# ProPrj_usb__2025-12-14-12-24-50.net
KiCad netlist of a schematic drawn in EasyEDA Pro
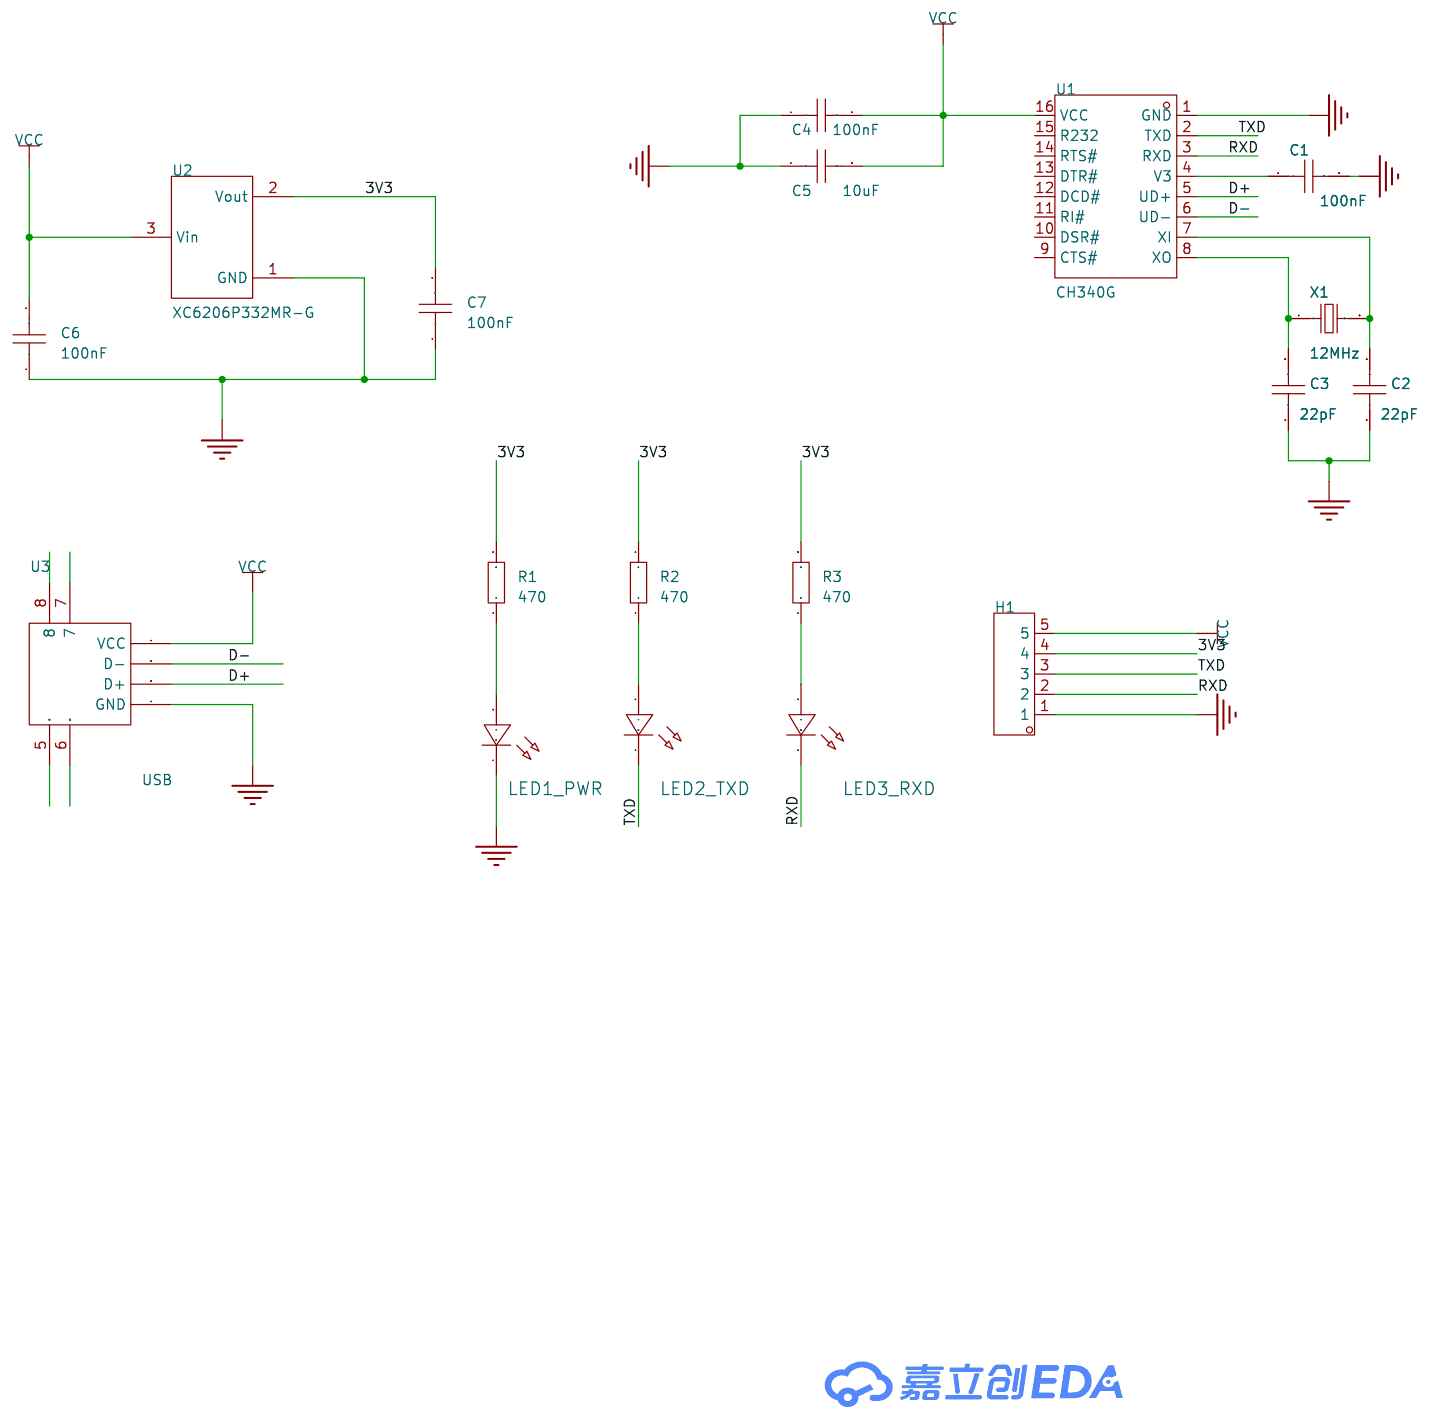
[diagram p0: schematic sheet]

(export (version "E")
  (design (tool "Eeschema 10.0.6"))
  (components
    (comp (ref "C1")
      (value "100nF")
      (footprint "easyedapro:C0603")
      (libsource (lib "easyedapro") (part "Capacitance"))
    )
    (comp (ref "C2")
      (value "22pF")
      (footprint "easyedapro:C0603")
      (libsource (lib "easyedapro") (part "Capacitance"))
    )
    (comp (ref "C3")
      (value "22pF")
      (footprint "easyedapro:C0603")
      (libsource (lib "easyedapro") (part "Capacitance"))
    )
    (comp (ref "C4")
      (value "100nF")
      (footprint "easyedapro:C0603")
      (libsource (lib "easyedapro") (part "Capacitance"))
    )
    (comp (ref "C5")
      (value "10uF")
      (footprint "easyedapro:C0603")
      (libsource (lib "easyedapro") (part "Capacitance"))
    )
    (comp (ref "C6")
      (value "100nF")
      (footprint "easyedapro:C0603")
      (libsource (lib "easyedapro") (part "Capacitance"))
    )
    (comp (ref "C7")
      (value "100nF")
      (footprint "easyedapro:C0603")
      (libsource (lib "easyedapro") (part "Capacitance"))
    )
    (comp (ref "H1")
      (value "~")
      (footprint "easyedapro:HDR-TH_5P-P2.54-V-M")
      (libsource (lib "easyedapro") (part "MTP125-1105S1"))
    )
    (comp (ref "LED1_PWR")
      (value "~")
      (footprint "easyedapro:LED_0603")
      (libsource (lib "easyedapro") (part "LED_R"))
    )
    (comp (ref "LED2_TXD")
      (value "~")
      (footprint "easyedapro:LED_0603")
      (libsource (lib "easyedapro") (part "LED_R"))
    )
    (comp (ref "LED3_RXD")
      (value "~")
      (footprint "easyedapro:LED_0603")
      (libsource (lib "easyedapro") (part "LED_R"))
    )
    (comp (ref "R1") (value "470") (footprint "easyedapro:R0603") (libsource (lib "easyedapro") (part "电阻")))
    (comp (ref "R2") (value "470") (footprint "easyedapro:R0603") (libsource (lib "easyedapro") (part "电阻")))
    (comp (ref "R3") (value "470") (footprint "easyedapro:R0603") (libsource (lib "easyedapro") (part "电阻")))
    (comp (ref "U1")
      (value "CH340G")
      (footprint "easyedapro:SOIC-16_L9.9-W3.9-P1.27-LS6.0-BL")
      (description "应用功能:USB转UART;接口协议:USB 2.0;数据速率:2Mbps;")
      (fields (field (name "Manufacturer") "WCH(南京沁恒)"))
      (libsource (lib "easyedapro") (part "CH340G"))
    )
    (comp (ref "U2")
      (value "XC6206P332MR-G")
      (footprint "easyedapro:SOT-23-3_L2.9-W1.6-P1.90-LS2.8-BR")
      (description "输出类型:固定;工作电压:6V;输出电压:3.3V;输出电流:200mA;电源纹波抑制比(PSRR):-;输出极性:正极;")
      (fields (field (name "Manufacturer") "TOREX(特瑞仕)"))
      (libsource (lib "easyedapro") (part "XC6206P332MR"))
    )
    (comp (ref "U3")
      (value "USB")
      (footprint "easyedapro:USB-SMD_USB_1")
      (libsource (lib "easyedapro") (part "USB"))
    )
    (comp (ref "X1")
      (value "12MHz")
      (footprint "easyedapro:CRYSTAL-SMD_L5.0-W3.2")
      (description "晶振类型:贴片晶振;频率:12MHz;常温频差:±20ppm;负载电容:20pF;频率稳定度:±30ppm;")
      (fields
        (field (name "Manufacturer Part") "XC53G2-12.000-F20LJDT")
        (field (name "Manufacturer") "HCI(杭晶)")
      )
      (libsource (lib "easyedapro") (part "XC53G2-12.000-F20LJDT"))
    )
  )
  (nets
    (net (code "1") (name "/3V3") (class "Default")
      (node (ref "C7") (pin "2") (pinfunction "2_2") (pintype "input"))
      (node (ref "H1") (pin "4") (pinfunction "4_4") (pintype "unspecified"))
      (node (ref "R1") (pin "2") (pinfunction "2_2") (pintype "input"))
      (node (ref "R2") (pin "2") (pinfunction "2_2") (pintype "input"))
      (node (ref "R3") (pin "2") (pinfunction "2_2") (pintype "input"))
      (node (ref "U2") (pin "2") (pinfunction "Vout_2") (pintype "unspecified"))
    )
    (net (code "2") (name "/D+") (class "Default")
      (node (ref "U1") (pin "5") (pinfunction "UD+_5") (pintype "unspecified"))
      (node (ref "U3") (pin "3") (pinfunction "D+_3") (pintype "input"))
    )
    (net (code "3") (name "/D-") (class "Default")
      (node (ref "U1") (pin "6") (pinfunction "UD-_6") (pintype "unspecified"))
      (node (ref "U3") (pin "2") (pinfunction "D-_2") (pintype "input"))
    )
    (net (code "4") (name "/RXD") (class "Default")
      (node (ref "H1") (pin "2") (pinfunction "2_2") (pintype "unspecified"))
      (node (ref "LED3_RXD") (pin "1") (pinfunction "C_1") (pintype "input"))
      (node (ref "U1") (pin "3") (pinfunction "RXD_3") (pintype "unspecified"))
    )
    (net (code "5") (name "/TXD") (class "Default")
      (node (ref "H1") (pin "3") (pinfunction "3_3") (pintype "unspecified"))
      (node (ref "LED2_TXD") (pin "1") (pinfunction "C_1") (pintype "input"))
      (node (ref "U1") (pin "2") (pinfunction "TXD_2") (pintype "unspecified"))
    )
    (net (code "6") (name "GND") (class "Default")
      (node (ref "C1") (pin "2") (pinfunction "2_2") (pintype "input"))
      (node (ref "C2") (pin "1") (pinfunction "1_1") (pintype "input"))
      (node (ref "C3") (pin "1") (pinfunction "1_1") (pintype "input"))
      (node (ref "C4") (pin "1") (pinfunction "1_1") (pintype "input"))
      (node (ref "C5") (pin "1") (pinfunction "1_1") (pintype "input"))
      (node (ref "C6") (pin "1") (pinfunction "1_1") (pintype "input"))
      (node (ref "C7") (pin "1") (pinfunction "1_1") (pintype "input"))
      (node (ref "H1") (pin "1") (pinfunction "1_1") (pintype "unspecified"))
      (node (ref "LED1_PWR") (pin "1") (pinfunction "C_1") (pintype "input"))
      (node (ref "U1") (pin "1") (pinfunction "GND_1") (pintype "unspecified"))
      (node (ref "U2") (pin "1") (pinfunction "GND_1") (pintype "unspecified"))
      (node (ref "U3") (pin "4") (pinfunction "GND_4") (pintype "input"))
    )
    (net (code "7") (name "Net-(LED1_PWR-A)") (class "Default")
      (node (ref "LED1_PWR") (pin "2") (pinfunction "A_2") (pintype "input"))
      (node (ref "R1") (pin "1") (pinfunction "1_1") (pintype "input"))
    )
    (net (code "8") (name "Net-(LED2_TXD-A)") (class "Default")
      (node (ref "LED2_TXD") (pin "2") (pinfunction "A_2") (pintype "input"))
      (node (ref "R2") (pin "1") (pinfunction "1_1") (pintype "input"))
    )
    (net (code "9") (name "Net-(LED3_RXD-A)") (class "Default")
      (node (ref "LED3_RXD") (pin "2") (pinfunction "A_2") (pintype "input"))
      (node (ref "R3") (pin "1") (pinfunction "1_1") (pintype "input"))
    )
    (net (code "10") (name "Net-(U1-V3)") (class "Default")
      (node (ref "C1") (pin "1") (pinfunction "1_1") (pintype "input"))
      (node (ref "U1") (pin "4") (pinfunction "V3_4") (pintype "unspecified"))
    )
    (net (code "11") (name "Net-(U1-XI)") (class "Default")
      (node (ref "C2") (pin "2") (pinfunction "2_2") (pintype "input"))
      (node (ref "U1") (pin "7") (pinfunction "XI_7") (pintype "unspecified"))
      (node (ref "X1") (pin "2") (pinfunction "2_2") (pintype "unspecified"))
    )
    (net (code "12") (name "Net-(U1-XO)") (class "Default")
      (node (ref "C3") (pin "2") (pinfunction "2_2") (pintype "input"))
      (node (ref "U1") (pin "8") (pinfunction "XO_8") (pintype "unspecified"))
      (node (ref "X1") (pin "1") (pinfunction "1_1") (pintype "unspecified"))
    )
    (net (code "13") (name "VCC") (class "Default")
      (node (ref "C4") (pin "2") (pinfunction "2_2") (pintype "input"))
      (node (ref "C5") (pin "2") (pinfunction "2_2") (pintype "input"))
      (node (ref "C6") (pin "2") (pinfunction "2_2") (pintype "input"))
      (node (ref "H1") (pin "5") (pinfunction "5_5") (pintype "unspecified"))
      (node (ref "U1") (pin "16") (pinfunction "VCC_16") (pintype "unspecified"))
      (node (ref "U2") (pin "3") (pinfunction "Vin_3") (pintype "unspecified"))
      (node (ref "U3") (pin "1") (pinfunction "VCC_1") (pintype "input"))
    )
    (net (code "14") (name "unconnected-(U1-CTS#-Pad9)") (class "Default")
      (node (ref "U1") (pin "9") (pinfunction "CTS#_9") (pintype "unspecified"))
    )
    (net (code "15") (name "unconnected-(U1-DCD#-Pad12)") (class "Default")
      (node (ref "U1") (pin "12") (pinfunction "DCD#_12") (pintype "unspecified"))
    )
    (net (code "16") (name "unconnected-(U1-DSR#-Pad10)") (class "Default")
      (node (ref "U1") (pin "10") (pinfunction "DSR#_10") (pintype "unspecified"))
    )
    (net (code "17") (name "unconnected-(U1-DTR#-Pad13)") (class "Default")
      (node (ref "U1") (pin "13") (pinfunction "DTR#_13") (pintype "unspecified"))
    )
    (net (code "18") (name "unconnected-(U1-R232-Pad15)") (class "Default")
      (node (ref "U1") (pin "15") (pinfunction "R232_15") (pintype "unspecified"))
    )
    (net (code "19") (name "unconnected-(U1-RI#-Pad11)") (class "Default")
      (node (ref "U1") (pin "11") (pinfunction "RI#_11") (pintype "unspecified"))
    )
    (net (code "20") (name "unconnected-(U1-RTS#-Pad14)") (class "Default")
      (node (ref "U1") (pin "14") (pinfunction "RTS#_14") (pintype "unspecified"))
    )
    (net (code "21") (name "unconnected-(U3-Pad7)") (class "Default")
      (node (ref "U3") (pin "7") (pinfunction "7_7") (pintype "unspecified"))
    )
    (net (code "22") (name "unconnected-(U3-Pad8)") (class "Default")
      (node (ref "U3") (pin "8") (pinfunction "8_8") (pintype "unspecified"))
    )
    (net (code "23") (name "unconnected-(U3-SH1-Pad5)") (class "Default")
      (node (ref "U3") (pin "5") (pinfunction "SH1_5") (pintype "unspecified"))
    )
    (net (code "24") (name "unconnected-(U3-SH2-Pad6)") (class "Default")
      (node (ref "U3") (pin "6") (pinfunction "SH2_6") (pintype "unspecified"))
    )
  )
)
